# nfc-epd-eink.net
KiCad netlist of a schematic drawn in Altium Designer
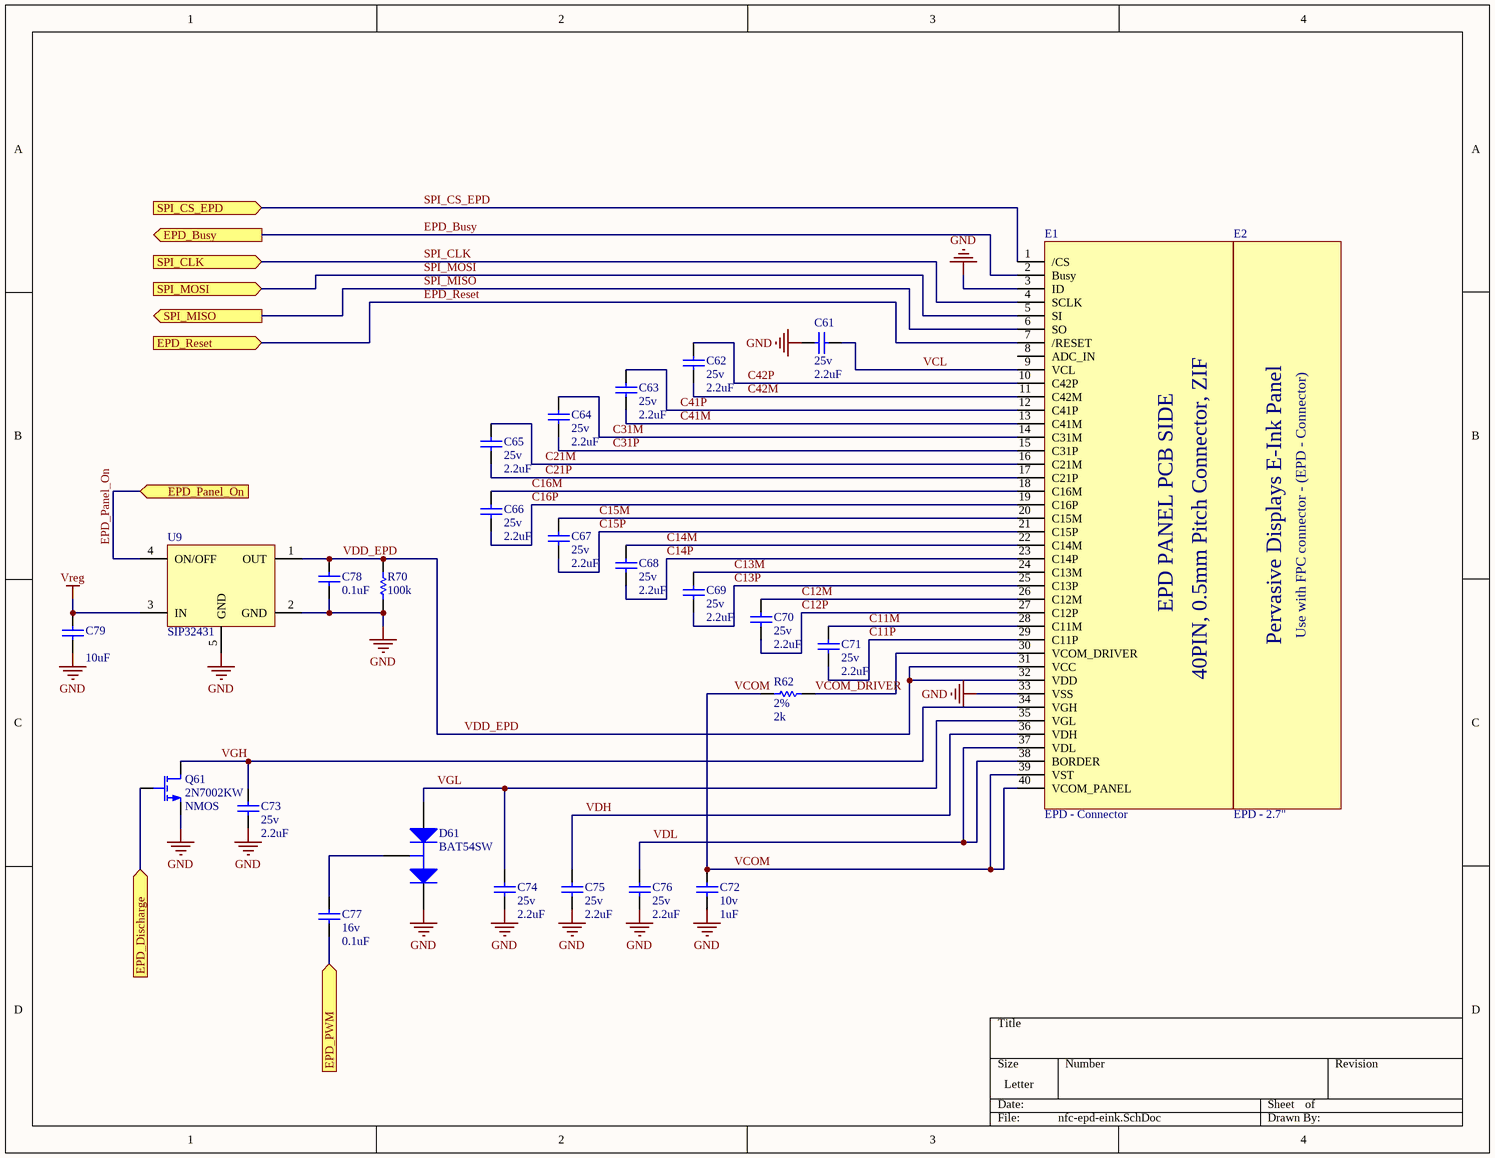
[diagram p0: nfc-epd-eink.SchDoc]

(export (version "E")
  (design (tool "Eeschema 10.0.6"))
  (components
    (comp (ref "C61")
      (value "2.2uF")
      (footprint "0402")
      (description "Ceramic Capacitor (Surface Mount)")
      (fields
        (field (name "MANUFACTURER") "Generic Ceramic Chip Cap (TBD)")
        (field (name "RATING") "25v")
        (field (name "Comment") "Cap")
      )
      (libsource (lib "WISP_AD10") (part "Cap"))
    )
    (comp (ref "C62")
      (value "2.2uF")
      (footprint "0402")
      (description "Ceramic Capacitor (Surface Mount)")
      (fields
        (field (name "MANUFACTURER") "Generic Ceramic Chip Cap (TBD)")
        (field (name "RATING") "25v")
        (field (name "Comment") "Cap")
      )
      (libsource (lib "WISP_AD10") (part "Cap"))
    )
    (comp (ref "C63")
      (value "2.2uF")
      (footprint "0402")
      (description "Ceramic Capacitor (Surface Mount)")
      (fields
        (field (name "MANUFACTURER") "Generic Ceramic Chip Cap (TBD)")
        (field (name "RATING") "25v")
        (field (name "Comment") "Cap")
      )
      (libsource (lib "WISP_AD10") (part "Cap"))
    )
    (comp (ref "C64")
      (value "2.2uF")
      (footprint "0402")
      (description "Ceramic Capacitor (Surface Mount)")
      (fields
        (field (name "MANUFACTURER") "Generic Ceramic Chip Cap (TBD)")
        (field (name "RATING") "25v")
        (field (name "Comment") "Cap")
      )
      (libsource (lib "WISP_AD10") (part "Cap"))
    )
    (comp (ref "C65")
      (value "2.2uF")
      (footprint "0402")
      (description "Ceramic Capacitor (Surface Mount)")
      (fields
        (field (name "MANUFACTURER") "Generic Ceramic Chip Cap (TBD)")
        (field (name "RATING") "25v")
        (field (name "Comment") "Cap")
      )
      (libsource (lib "WISP_AD10") (part "Cap"))
    )
    (comp (ref "C66")
      (value "2.2uF")
      (footprint "0402")
      (description "Ceramic Capacitor (Surface Mount)")
      (fields
        (field (name "MANUFACTURER") "Generic Ceramic Chip Cap (TBD)")
        (field (name "RATING") "25v")
        (field (name "Comment") "Cap")
      )
      (libsource (lib "WISP_AD10") (part "Cap"))
    )
    (comp (ref "C67")
      (value "2.2uF")
      (footprint "0402")
      (description "Ceramic Capacitor (Surface Mount)")
      (fields
        (field (name "MANUFACTURER") "Generic Ceramic Chip Cap (TBD)")
        (field (name "RATING") "25v")
        (field (name "Comment") "Cap")
      )
      (libsource (lib "WISP_AD10") (part "Cap"))
    )
    (comp (ref "C68")
      (value "2.2uF")
      (footprint "0402")
      (description "Ceramic Capacitor (Surface Mount)")
      (fields
        (field (name "MANUFACTURER") "Generic Ceramic Chip Cap (TBD)")
        (field (name "RATING") "25v")
        (field (name "Comment") "Cap")
      )
      (libsource (lib "WISP_AD10") (part "Cap"))
    )
    (comp (ref "C69")
      (value "2.2uF")
      (footprint "0402")
      (description "Ceramic Capacitor (Surface Mount)")
      (fields
        (field (name "MANUFACTURER") "Generic Ceramic Chip Cap (TBD)")
        (field (name "RATING") "25v")
        (field (name "Comment") "Cap")
      )
      (libsource (lib "WISP_AD10") (part "Cap"))
    )
    (comp (ref "C70")
      (value "2.2uF")
      (footprint "0402")
      (description "Ceramic Capacitor (Surface Mount)")
      (fields
        (field (name "MANUFACTURER") "Generic Ceramic Chip Cap (TBD)")
        (field (name "RATING") "25v")
        (field (name "Comment") "Cap")
      )
      (libsource (lib "WISP_AD10") (part "Cap"))
    )
    (comp (ref "C71")
      (value "2.2uF")
      (footprint "0402")
      (description "Ceramic Capacitor (Surface Mount)")
      (fields
        (field (name "MANUFACTURER") "Generic Ceramic Chip Cap (TBD)")
        (field (name "RATING") "25v")
        (field (name "Comment") "Cap")
      )
      (libsource (lib "WISP_AD10") (part "Cap"))
    )
    (comp (ref "C72")
      (value "1uF")
      (footprint "0603")
      (description "Ceramic Capacitor (Surface Mount)")
      (fields
        (field (name "MANUFACTURER") "Generic Ceramic Chip Cap (TBD)")
        (field (name "RATING") "10v")
        (field (name "Comment") "Cap")
      )
      (libsource (lib "WISP_AD10") (part "Cap"))
    )
    (comp (ref "C73")
      (value "2.2uF")
      (footprint "0603")
      (description "Ceramic Capacitor (Surface Mount)")
      (fields
        (field (name "MANUFACTURER") "Generic Ceramic Chip Cap (TBD)")
        (field (name "RATING") "25v")
        (field (name "Comment") "Cap")
      )
      (libsource (lib "WISP_AD10") (part "Cap"))
    )
    (comp (ref "C74")
      (value "2.2uF")
      (footprint "0603")
      (description "Ceramic Capacitor (Surface Mount)")
      (fields
        (field (name "MANUFACTURER") "Generic Ceramic Chip Cap (TBD)")
        (field (name "RATING") "25v")
        (field (name "Comment") "Cap")
      )
      (libsource (lib "WISP_AD10") (part "Cap"))
    )
    (comp (ref "C75")
      (value "2.2uF")
      (footprint "0603")
      (description "Ceramic Capacitor (Surface Mount)")
      (fields
        (field (name "MANUFACTURER") "Generic Ceramic Chip Cap (TBD)")
        (field (name "RATING") "25v")
        (field (name "Comment") "Cap")
      )
      (libsource (lib "WISP_AD10") (part "Cap"))
    )
    (comp (ref "C76")
      (value "2.2uF")
      (footprint "0603")
      (description "Ceramic Capacitor (Surface Mount)")
      (fields
        (field (name "MANUFACTURER") "Generic Ceramic Chip Cap (TBD)")
        (field (name "RATING") "25v")
        (field (name "Comment") "Cap")
      )
      (libsource (lib "WISP_AD10") (part "Cap"))
    )
    (comp (ref "C77")
      (value "0.1uF")
      (footprint "0603")
      (description "Ceramic Capacitor (Surface Mount)")
      (fields
        (field (name "MANUFACTURER") "Generic Ceramic Chip Cap (TBD)")
        (field (name "RATING") "16v")
        (field (name "Comment") "Cap")
      )
      (libsource (lib "WISP_AD10") (part "Cap"))
    )
    (comp (ref "C78")
      (value "0.1uF")
      (footprint "0603")
      (description "Ceramic Capacitor (Surface Mount)")
      (fields (field (name "MANUFACTURER") "Generic Ceramic Chip Cap (TBD)") (field (name "Comment") "Cap"))
      (libsource (lib "WISP_AD10") (part "Cap"))
    )
    (comp (ref "C79")
      (value "10uF")
      (footprint "0603")
      (description "Ceramic Capacitor (Surface Mount)")
      (fields (field (name "MANUFACTURER") "Generic Ceramic Chip Cap (TBD)") (field (name "Comment") "Cap"))
      (libsource (lib "WISP_AD10") (part "Cap"))
    )
    (comp (ref "D61")
      (value "BAT54SW")
      (footprint "SOT-323 / SC-70")
      (description "Diode Array, Two in Series, Small Package SOT-323")
      (fields
        (field (name "MANUFACTURER") "ON Semiconductor")
        (field (name "MANUFACTURER PART NUMBER") "BAT54SWT1G")
      )
      (libsource (lib "WISP_AD10") (part "Diode - Array_1"))
    )
    (comp (ref "E1")
      (value "EPD - Connector")
      (footprint "EPD - Connector")
      (description "FPC, 40pin, 0.5mm Pitch - ZIF")
      (fields
        (field (name "MANUFACTURER") "Hirose Electric Co Ltd")
        (field (name "MANUFACTURER PART NUMBER") "FH12-40S-0.5SH or FH12S-40S-0.5SH")
      )
      (libsource (lib "WISP_AD10") (part "EPD - Connector"))
    )
    (comp (ref "E2")
      (value "EPD - 2.7\"")
      (footprint "EPD - EM027AS012")
      (description "2.7\" TFT EPD Panel, STARCONN 089H40 variant")
      (fields
        (field (name "DIGI-KEY PART NUMBER") "EA-LCD-009-ND (should find another supplyer)")
        (field (name "MANUFACTURER") "PERVASIVE DISPLAYS, INC")
      )
      (libsource (lib "WISP_AD10") (part "EPD - Display EM027AS012"))
    )
    (comp (ref "Q61")
      (value "2N7002KW")
      (footprint "SOT-323 / SC-70")
      (description "N-Channel MOSFET")
      (fields
        (field (name "DIGI-KEY PART NUMBER") "2N7002KWCT-ND")
        (field (name "MANUFACTURER") "Fairchild Semiconductor")
        (field (name "ALTIUM_VALUE") "NMOS")
      )
      (libsource (lib "WISP_AD10") (part "MOSFET-N"))
    )
    (comp (ref "R62")
      (value "2k")
      (footprint "0603")
      (description "Chip Resistor (Surface Mount)")
      (fields
        (field (name "MANUFACTURER") "Generic Chip Res (TBD)")
        (field (name "RATING") "2%")
        (field (name "Comment") "Res")
      )
      (libsource (lib "WISP_AD10") (part "Res"))
    )
    (comp (ref "R70")
      (value "100k")
      (footprint "0603")
      (description "Chip Resistor (Surface Mount)")
      (fields (field (name "MANUFACTURER") "Generic Chip Res (TBD)") (field (name "Comment") "Res"))
      (libsource (lib "WISP_AD10") (part "Res"))
    )
    (comp (ref "U9")
      (value "SIP32431")
      (footprint "TDFN-4")
      (description "High Sside Switch - 4TDFN package")
      (fields
        (field (name "DIGI-KEY PART NUMBER") "SIP32431DNP3-T1GE4CT-ND")
        (field (name "MANUFACTURER") "Vishay Siliconix")
      )
      (libsource (lib "WISP_AD10") (part "SIP32431"))
    )
  )
  (nets
    (net (code "1") (name "/C11M") (class "Default")
      (node (ref "C71") (pin "2") (pinfunction "2_2") (pintype "passive"))
      (node (ref "E1") (pin "28") (pinfunction "C11M_28") (pintype "passive"))
    )
    (net (code "2") (name "/C11P") (class "Default")
      (node (ref "C71") (pin "1") (pinfunction "1_1") (pintype "passive"))
      (node (ref "E1") (pin "29") (pinfunction "C11P_29") (pintype "passive"))
    )
    (net (code "3") (name "/C12M") (class "Default")
      (node (ref "C70") (pin "1") (pinfunction "1_1") (pintype "passive"))
      (node (ref "E1") (pin "26") (pinfunction "C12M_26") (pintype "passive"))
    )
    (net (code "4") (name "/C12P") (class "Default")
      (node (ref "C70") (pin "2") (pinfunction "2_2") (pintype "passive"))
      (node (ref "E1") (pin "27") (pinfunction "C12P_27") (pintype "passive"))
    )
    (net (code "5") (name "/C13M") (class "Default")
      (node (ref "C69") (pin "2") (pinfunction "2_2") (pintype "passive"))
      (node (ref "E1") (pin "24") (pinfunction "C13M_24") (pintype "passive"))
    )
    (net (code "6") (name "/C13P") (class "Default")
      (node (ref "C69") (pin "1") (pinfunction "1_1") (pintype "passive"))
      (node (ref "E1") (pin "25") (pinfunction "C13P_25") (pintype "passive"))
    )
    (net (code "7") (name "/C14M") (class "Default")
      (node (ref "C68") (pin "2") (pinfunction "2_2") (pintype "passive"))
      (node (ref "E1") (pin "22") (pinfunction "C14M_22") (pintype "passive"))
    )
    (net (code "8") (name "/C14P") (class "Default")
      (node (ref "C68") (pin "1") (pinfunction "1_1") (pintype "passive"))
      (node (ref "E1") (pin "23") (pinfunction "C14P_23") (pintype "passive"))
    )
    (net (code "9") (name "/C15M") (class "Default")
      (node (ref "C67") (pin "2") (pinfunction "2_2") (pintype "passive"))
      (node (ref "E1") (pin "20") (pinfunction "C15M_20") (pintype "passive"))
    )
    (net (code "10") (name "/C15P") (class "Default")
      (node (ref "C67") (pin "1") (pinfunction "1_1") (pintype "passive"))
      (node (ref "E1") (pin "21") (pinfunction "C15P_21") (pintype "passive"))
    )
    (net (code "11") (name "/C16M") (class "Default")
      (node (ref "C66") (pin "2") (pinfunction "2_2") (pintype "passive"))
      (node (ref "E1") (pin "18") (pinfunction "C16M_18") (pintype "passive"))
    )
    (net (code "12") (name "/C16P") (class "Default")
      (node (ref "C66") (pin "1") (pinfunction "1_1") (pintype "passive"))
      (node (ref "E1") (pin "19") (pinfunction "C16P_19") (pintype "passive"))
    )
    (net (code "13") (name "/C21M") (class "Default")
      (node (ref "C65") (pin "2") (pinfunction "2_2") (pintype "passive"))
      (node (ref "E1") (pin "16") (pinfunction "C21M_16") (pintype "passive"))
    )
    (net (code "14") (name "/C21P") (class "Default")
      (node (ref "C65") (pin "1") (pinfunction "1_1") (pintype "passive"))
      (node (ref "E1") (pin "17") (pinfunction "C21P_17") (pintype "passive"))
    )
    (net (code "15") (name "/C31M") (class "Default")
      (node (ref "C64") (pin "2") (pinfunction "2_2") (pintype "passive"))
      (node (ref "E1") (pin "14") (pinfunction "C31M_14") (pintype "passive"))
    )
    (net (code "16") (name "/C31P") (class "Default")
      (node (ref "C64") (pin "1") (pinfunction "1_1") (pintype "passive"))
      (node (ref "E1") (pin "15") (pinfunction "C31P_15") (pintype "passive"))
    )
    (net (code "17") (name "/C41M") (class "Default")
      (node (ref "C63") (pin "1") (pinfunction "1_1") (pintype "passive"))
      (node (ref "E1") (pin "13") (pinfunction "C41M_13") (pintype "passive"))
    )
    (net (code "18") (name "/C41P") (class "Default")
      (node (ref "C63") (pin "2") (pinfunction "2_2") (pintype "passive"))
      (node (ref "E1") (pin "12") (pinfunction "C41P_12") (pintype "passive"))
    )
    (net (code "19") (name "/C42M") (class "Default")
      (node (ref "C62") (pin "2") (pinfunction "2_2") (pintype "passive"))
      (node (ref "E1") (pin "11") (pinfunction "C42M_11") (pintype "passive"))
    )
    (net (code "20") (name "/C42P") (class "Default")
      (node (ref "C62") (pin "1") (pinfunction "1_1") (pintype "passive"))
      (node (ref "E1") (pin "10") (pinfunction "C42P_10") (pintype "passive"))
    )
    (net (code "21") (name "/EPD_Busy") (class "Default")
      (node (ref "E1") (pin "2") (pinfunction "Busy_2") (pintype "passive"))
    )
    (net (code "22") (name "/EPD_Discharge") (class "Default")
      (node (ref "Q61") (pin "1") (pinfunction "G_1") (pintype "passive"))
    )
    (net (code "23") (name "/EPD_PWM") (class "Default")
      (node (ref "C77") (pin "1") (pinfunction "1_1") (pintype "passive"))
    )
    (net (code "24") (name "/EPD_Panel_On") (class "Default")
      (node (ref "U9") (pin "4") (pinfunction "ON/OFF_4") (pintype "passive"))
    )
    (net (code "25") (name "/EPD_Reset") (class "Default")
      (node (ref "E1") (pin "7") (pinfunction "/RESET_7") (pintype "passive"))
    )
    (net (code "26") (name "/SPI_CLK") (class "Default")
      (node (ref "E1") (pin "4") (pinfunction "SCLK_4") (pintype "passive"))
    )
    (net (code "27") (name "/SPI_CS_EPD") (class "Default")
      (node (ref "E1") (pin "1") (pinfunction "/CS_1") (pintype "passive"))
    )
    (net (code "28") (name "/SPI_MISO") (class "Default")
      (node (ref "E1") (pin "6") (pinfunction "SO_6") (pintype "passive"))
    )
    (net (code "29") (name "/SPI_MOSI") (class "Default")
      (node (ref "E1") (pin "5") (pinfunction "SI_5") (pintype "passive"))
    )
    (net (code "30") (name "/VCL") (class "Default")
      (node (ref "C61") (pin "1") (pinfunction "1_1") (pintype "passive"))
      (node (ref "E1") (pin "9") (pinfunction "VCL_9") (pintype "passive"))
    )
    (net (code "31") (name "/VCOM") (class "Default")
      (node (ref "C72") (pin "2") (pinfunction "2_2") (pintype "passive"))
      (node (ref "E1") (pin "39") (pinfunction "VST_39") (pintype "passive"))
      (node (ref "E1") (pin "40") (pinfunction "VCOM_PANEL_40") (pintype "passive"))
      (node (ref "R62") (pin "2") (pinfunction "2_2") (pintype "passive"))
    )
    (net (code "32") (name "/VCOM_DRIVER") (class "Default")
      (node (ref "E1") (pin "30") (pinfunction "VCOM_DRIVER_30") (pintype "passive"))
      (node (ref "R62") (pin "1") (pinfunction "1_1") (pintype "passive"))
    )
    (net (code "33") (name "/VDD_EPD") (class "Default")
      (node (ref "C78") (pin "2") (pinfunction "2_2") (pintype "passive"))
      (node (ref "E1") (pin "31") (pinfunction "VCC_31") (pintype "passive"))
      (node (ref "E1") (pin "32") (pinfunction "VDD_32") (pintype "passive"))
      (node (ref "R70") (pin "2") (pinfunction "2_2") (pintype "passive"))
      (node (ref "U9") (pin "1") (pinfunction "OUT_1") (pintype "passive"))
    )
    (net (code "34") (name "/VDH") (class "Default")
      (node (ref "C75") (pin "2") (pinfunction "2_2") (pintype "passive"))
      (node (ref "E1") (pin "36") (pinfunction "VDH_36") (pintype "passive"))
    )
    (net (code "35") (name "/VDL") (class "Default")
      (node (ref "C76") (pin "2") (pinfunction "2_2") (pintype "passive"))
      (node (ref "E1") (pin "37") (pinfunction "VDL_37") (pintype "passive"))
      (node (ref "E1") (pin "38") (pinfunction "BORDER_38") (pintype "passive"))
    )
    (net (code "36") (name "/VGH") (class "Default")
      (node (ref "C73") (pin "2") (pinfunction "2_2") (pintype "passive"))
      (node (ref "E1") (pin "34") (pinfunction "VGH_34") (pintype "passive"))
      (node (ref "Q61") (pin "3") (pinfunction "D_3") (pintype "passive"))
    )
    (net (code "37") (name "/VGL") (class "Default")
      (node (ref "C74") (pin "2") (pinfunction "2_2") (pintype "passive"))
      (node (ref "D61") (pin "1") (pinfunction "A_1") (pintype "passive"))
      (node (ref "E1") (pin "35") (pinfunction "VGL_35") (pintype "passive"))
    )
    (net (code "38") (name "GND") (class "Default")
      (node (ref "C61") (pin "2") (pinfunction "2_2") (pintype "passive"))
      (node (ref "C72") (pin "1") (pinfunction "1_1") (pintype "passive"))
      (node (ref "C73") (pin "1") (pinfunction "1_1") (pintype "passive"))
      (node (ref "C74") (pin "1") (pinfunction "1_1") (pintype "passive"))
      (node (ref "C75") (pin "1") (pinfunction "1_1") (pintype "passive"))
      (node (ref "C76") (pin "1") (pinfunction "1_1") (pintype "passive"))
      (node (ref "C78") (pin "1") (pinfunction "1_1") (pintype "passive"))
      (node (ref "C79") (pin "1") (pinfunction "1_1") (pintype "passive"))
      (node (ref "D61") (pin "2") (pinfunction "K_2") (pintype "passive"))
      (node (ref "E1") (pin "3") (pinfunction "ID_3") (pintype "passive"))
      (node (ref "E1") (pin "33") (pinfunction "VSS_33") (pintype "passive"))
      (node (ref "Q61") (pin "2") (pinfunction "S_2") (pintype "passive"))
      (node (ref "R70") (pin "1") (pinfunction "1_1") (pintype "passive"))
      (node (ref "U9") (pin "2") (pinfunction "GND_2") (pintype "passive"))
      (node (ref "U9") (pin "5") (pinfunction "GND_5") (pintype "passive"))
    )
    (net (code "39") (name "Net-(D61-C)") (class "Default")
      (node (ref "C77") (pin "2") (pinfunction "2_2") (pintype "passive"))
      (node (ref "D61") (pin "3") (pinfunction "C_3") (pintype "passive"))
    )
    (net (code "40") (name "Vreg") (class "Default")
      (node (ref "C79") (pin "2") (pinfunction "2_2") (pintype "passive"))
      (node (ref "U9") (pin "3") (pinfunction "IN_3") (pintype "passive"))
    )
    (net (code "41") (name "unconnected-(E1-ADC_IN-Pad8)") (class "Default")
      (node (ref "E1") (pin "8") (pinfunction "ADC_IN_8") (pintype "passive"))
    )
  )
)
